# Regulador_LDO.net
KiCad netlist of a schematic drawn in Altium Designer
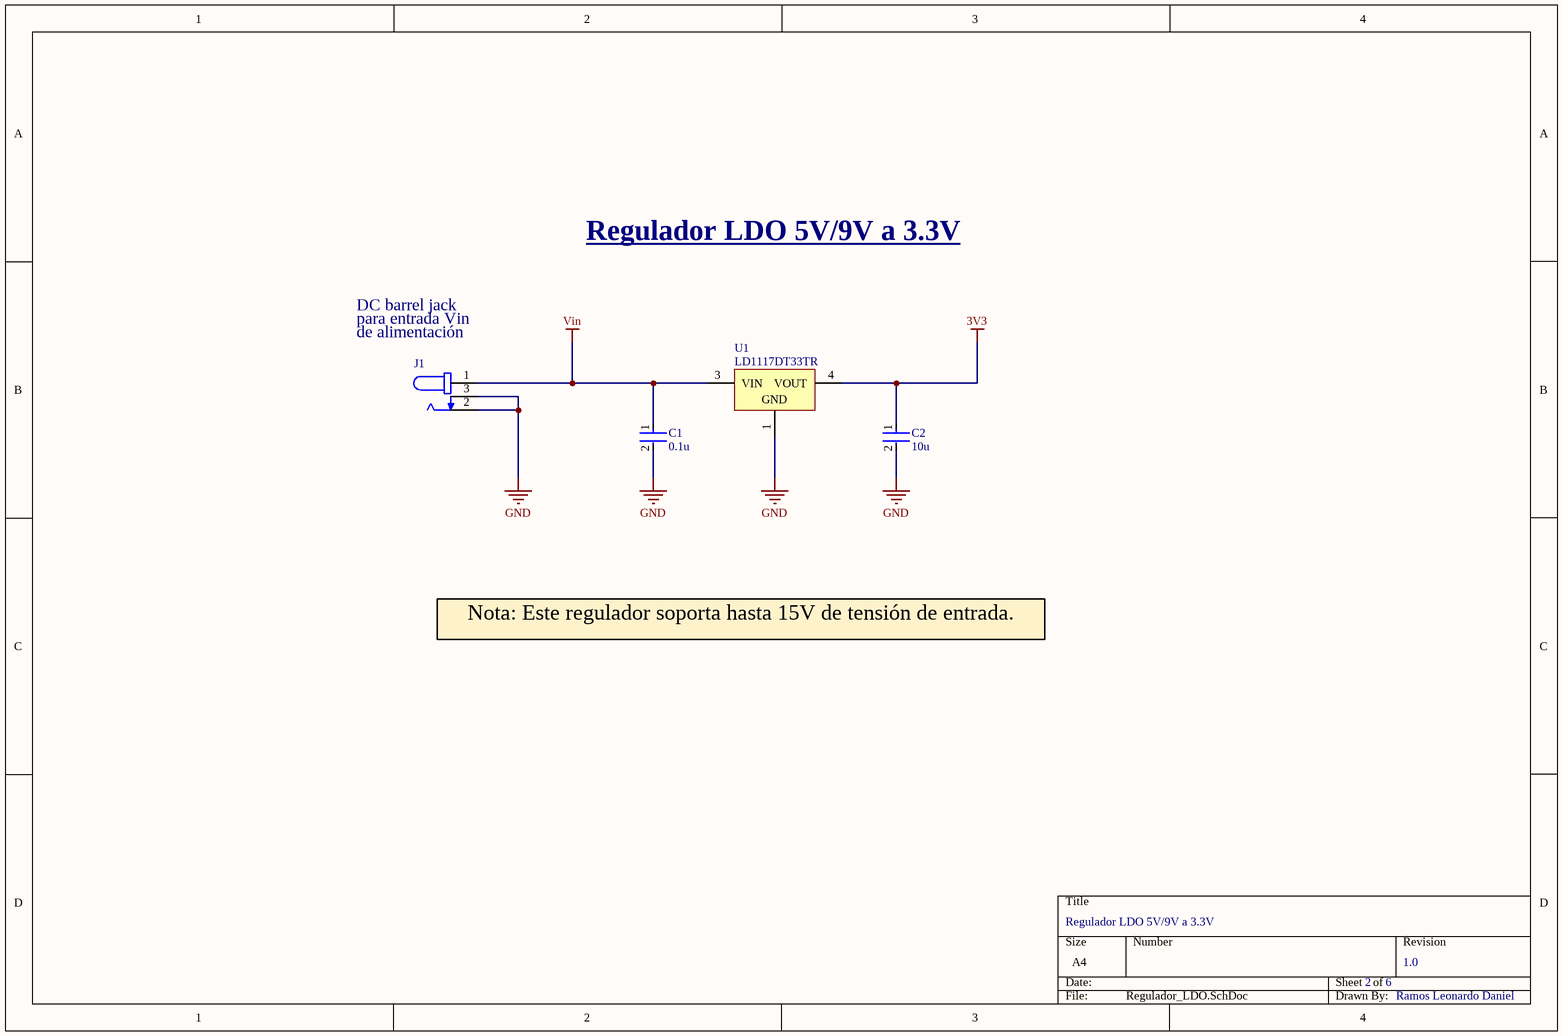
[diagram p0: Regulador_LDO.SchDoc]

(export (version "E")
  (design (tool "Eeschema 10.0.6"))
  (components
    (comp (ref "C1")
      (value "0.1u")
      (footprint "FP-GRM21B-0_1-IPC_B")
      (description "Chip Multilayer Ceramic Capacitors for General Purpose, 0805, 0.10uF, U2J, -750ppm/°C, 5%, 10V")
      (fields (field (name "TOLERANCE") "5%"))
      (libsource (lib "Altium Content Vault") (part "b4654b650e69147ec39a6b967a45e02"))
    )
    (comp (ref "C2")
      (value "10u")
      (footprint "FP-C0805C106J8RACAUTO-MFG")
      (description "CAP CER 10UF 10V X7R 0805")
      (fields (field (name "TOLERANCE") "5%"))
      (libsource (lib "Altium Content Vault") (part "02cd4be3c70576c341d710602a673aa"))
    )
    (comp (ref "J1")
      (value "DCJ200-10-A-XX-K_REVA")
      (footprint "GCT_DCJ200-10-A-XX-K_REVA")
      (description "Power Barrel Connector Jack 2.05mm ID (0.081), 5.50mm OD (0.217) Through Hole, Right Angle")
      (fields (field (name "MF") "Global Connector Technology") (field (name "MP") "DCJ200-10-A-K1-K"))
      (libsource (lib "Miscelaneos") (part "DCJ200-10-A-XX-K_REVA"))
    )
    (comp (ref "U1")
      (value "LD1117DT33TR")
      (footprint "TO-252_N")
      (description "Fixed Low Drop Positive Voltage Regulator, 3.3V, 3-Pin DPAK, Tape and Reel")
      (libsource (lib "Altium Content Vault") (part "PM-REG-LD1117-SOT3"))
    )
  )
  (nets
    (net (code "1") (name "3V3") (class "Default")
      (node (ref "C2") (pin "1") (pinfunction "1_1") (pintype "passive"))
      (node (ref "U1") (pin "4") (pinfunction "VOUT_4") (pintype "power_in"))
    )
    (net (code "2") (name "GND") (class "Default")
      (node (ref "C1") (pin "2") (pinfunction "2_2") (pintype "passive"))
      (node (ref "C2") (pin "2") (pinfunction "2_2") (pintype "passive"))
      (node (ref "J1") (pin "2") (pinfunction "2_2") (pintype "passive"))
      (node (ref "J1") (pin "3") (pinfunction "3_3") (pintype "passive"))
      (node (ref "U1") (pin "1") (pinfunction "GND_1") (pintype "power_in"))
    )
    (net (code "3") (name "Vin") (class "Default")
      (node (ref "C1") (pin "1") (pinfunction "1_1") (pintype "passive"))
      (node (ref "J1") (pin "1") (pinfunction "1_1") (pintype "passive"))
      (node (ref "U1") (pin "3") (pinfunction "VIN_3") (pintype "power_in"))
    )
  )
)
